# Adafruit_WINC1500_Breakout.net
KiCad netlist of a schematic drawn in EAGLE
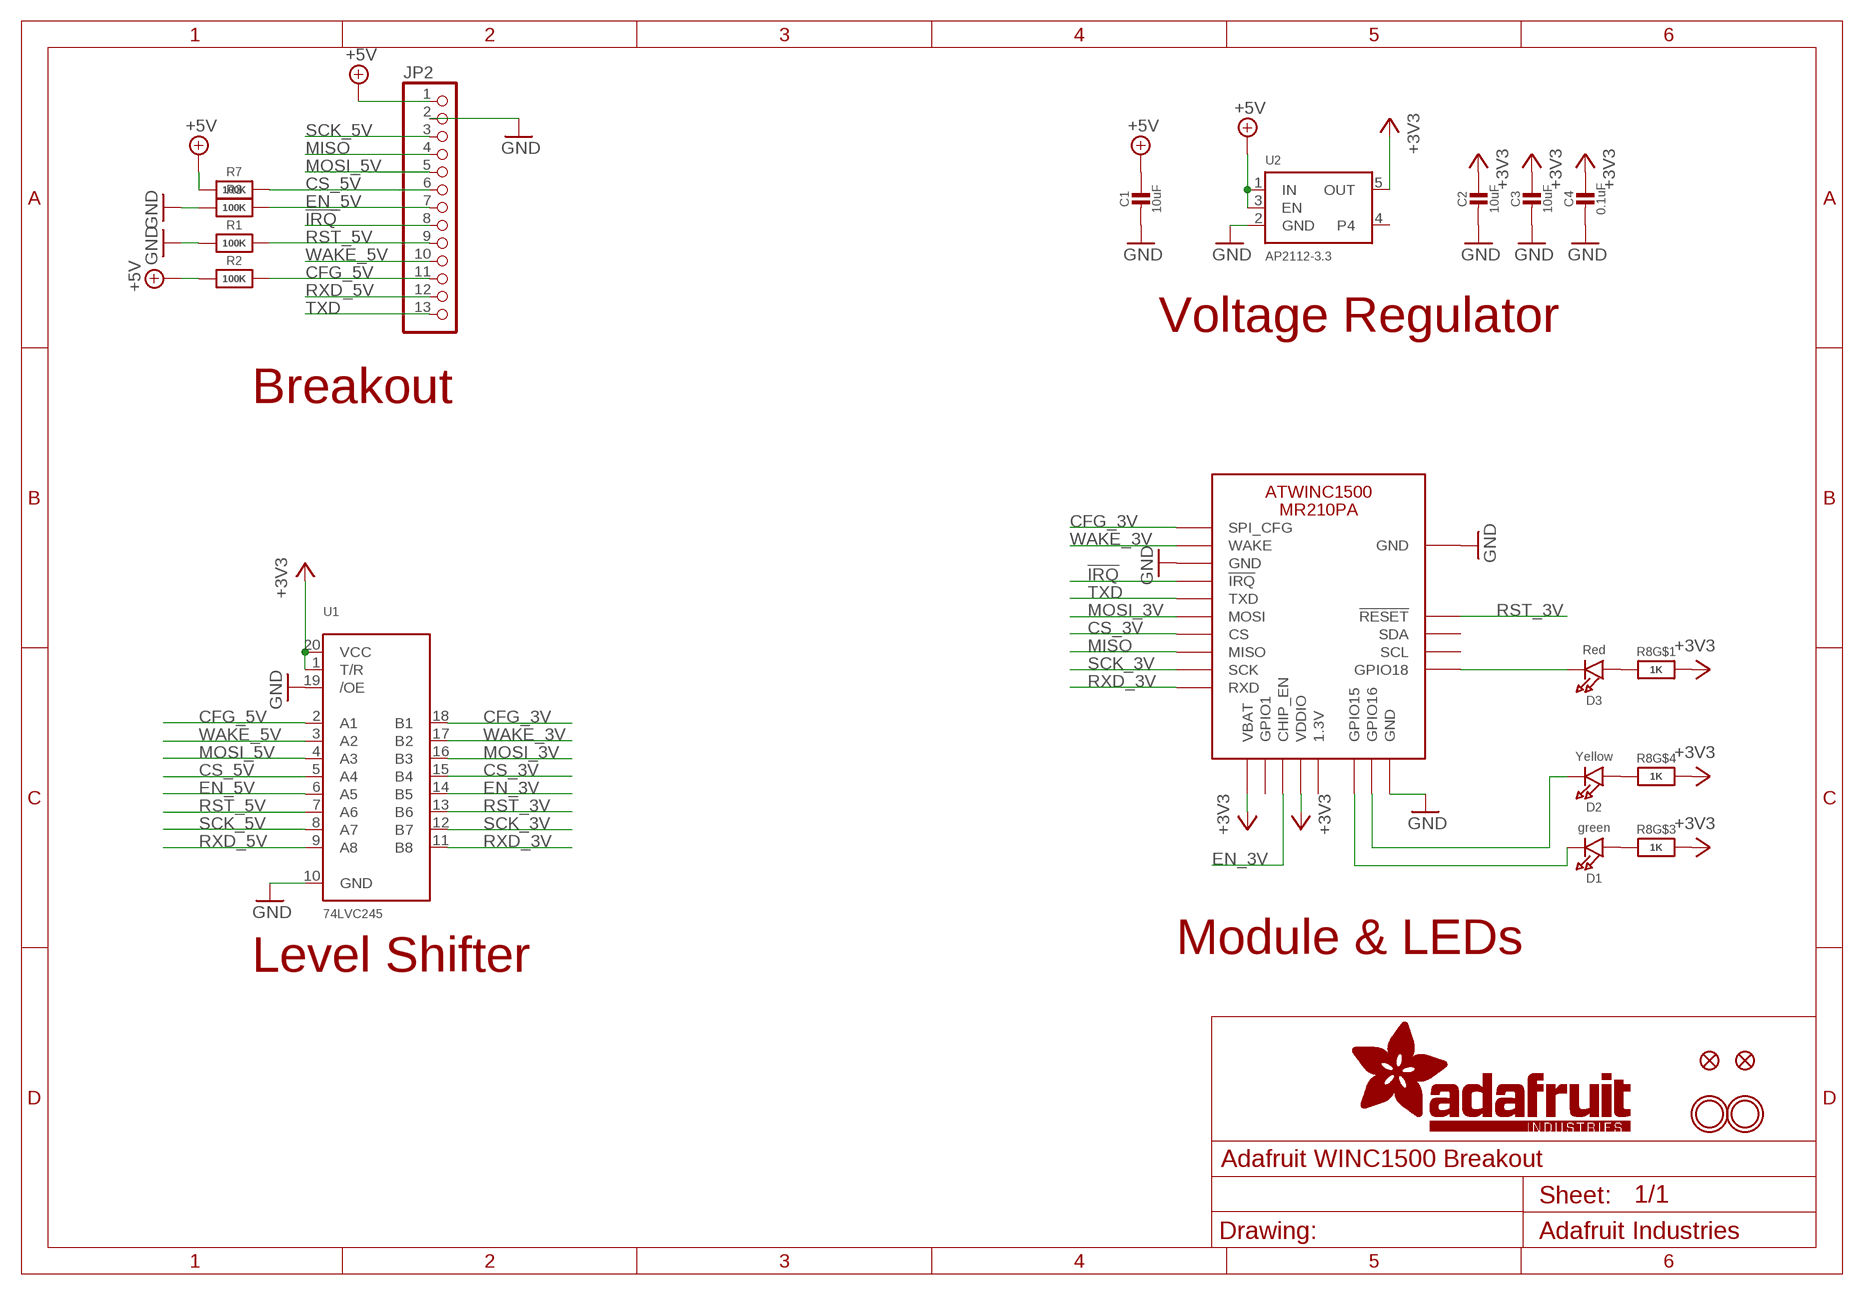
[diagram p0: schematic, sheet 1]

(export (version "E")
  (design (tool "Eeschema 10.0.6"))
  (components
    (comp (ref "C1")
      (value "10uF")
      (footprint "eagle-import:0805-NO")
      (libsource (lib "eagle-import") (part "CAP_CERAMIC0805-NOOUTLINE"))
    )
    (comp (ref "C2")
      (value "10uF")
      (footprint "eagle-import:0805_10MGAP")
      (libsource (lib "eagle-import") (part "CAP_CERAMIC0805_10MGAP"))
    )
    (comp (ref "C3")
      (value "10uF")
      (footprint "eagle-import:0805-NO")
      (libsource (lib "eagle-import") (part "CAP_CERAMIC0805-NOOUTLINE"))
    )
    (comp (ref "C4")
      (value "0.1uF")
      (footprint "eagle-import:0805-NO")
      (libsource (lib "eagle-import") (part "CAP_CERAMIC0805-NOOUTLINE"))
    )
    (comp (ref "D1")
      (value "green")
      (footprint "eagle-import:CHIPLED_0805_NOOUTLINE")
      (libsource (lib "eagle-import") (part "LED0805_NOOUTLINE"))
    )
    (comp (ref "D2")
      (value "Yellow")
      (footprint "eagle-import:CHIPLED_0805_NOOUTLINE")
      (libsource (lib "eagle-import") (part "LED0805_NOOUTLINE"))
    )
    (comp (ref "D3")
      (value "Red")
      (footprint "eagle-import:CHIPLED_0805_NOOUTLINE")
      (libsource (lib "eagle-import") (part "LED0805_NOOUTLINE"))
    )
    (comp (ref "FID1")
      (value "FIDUCIAL\"\"")
      (footprint "eagle-import:FIDUCIAL_1MM")
      (libsource (lib "eagle-import") (part "FIDUCIAL{dblquote}{dblquote}"))
    )
    (comp (ref "FID2")
      (value "FIDUCIAL\"\"")
      (footprint "eagle-import:FIDUCIAL_1MM")
      (libsource (lib "eagle-import") (part "FIDUCIAL{dblquote}{dblquote}"))
    )
    (comp (ref "JP2")
      (value "HEADER-1X13")
      (footprint "eagle-import:1X13_ROUND_70")
      (libsource (lib "eagle-import") (part "HEADER-1X13"))
    )
    (comp (ref "R1")
      (value "100K")
      (footprint "eagle-import:0805-NO")
      (libsource (lib "eagle-import") (part "RESISTOR0805_NOOUTLINE"))
    )
    (comp (ref "R2")
      (value "100K")
      (footprint "eagle-import:0805-NO")
      (libsource (lib "eagle-import") (part "RESISTOR0805_NOOUTLINE"))
    )
    (comp (ref "R3")
      (value "100K")
      (footprint "eagle-import:_0805MP")
      (libsource (lib "eagle-import") (part "RESISTOR_0805MP"))
    )
    (comp (ref "R7")
      (value "100K")
      (footprint "eagle-import:_0805MP")
      (libsource (lib "eagle-import") (part "RESISTOR_0805MP"))
    )
    (comp (ref "R8")
      (value "1K")
      (footprint "eagle-import:RESPACK_4X0603")
      (libsource (lib "eagle-import") (part "RESISTOR_4PACK"))
    )
    (comp (ref "U$1")
      (value "ATWINC1500_MR210PB")
      (footprint "eagle-import:ATWINC1500_MR210PA")
      (libsource (lib "eagle-import") (part "ATWINC1500_MR210PA"))
    )
    (comp (ref "U$2")
      (value "MOUNTINGHOLE2.5")
      (footprint "eagle-import:MOUNTINGHOLE_2.5_PLATED")
      (libsource (lib "eagle-import") (part "MOUNTINGHOLE2.5"))
    )
    (comp (ref "U$3")
      (value "MOUNTINGHOLE2.5")
      (footprint "eagle-import:MOUNTINGHOLE_2.5_PLATED")
      (libsource (lib "eagle-import") (part "MOUNTINGHOLE2.5"))
    )
    (comp (ref "U1")
      (value "74LVC245")
      (footprint "eagle-import:TSSOP20")
      (libsource (lib "eagle-import") (part "74LCX245"))
    )
    (comp (ref "U2")
      (value "AP2112-3.3")
      (footprint "eagle-import:SOT23-5")
      (libsource (lib "eagle-import") (part "VREG_SOT23-5"))
    )
  )
  (nets
    (net (code "1") (name "+3V3") (class "Default")
      (node (ref "C2") (pin "1") (pinfunction "1_1") (pintype "passive"))
      (node (ref "C3") (pin "1") (pinfunction "1_1") (pintype "passive"))
      (node (ref "C4") (pin "1") (pinfunction "1_1") (pintype "passive"))
      (node (ref "R8") (pin "5") (pinfunction "2_5") (pintype "passive"))
      (node (ref "R8") (pin "6") (pinfunction "2_6") (pintype "passive"))
      (node (ref "R8") (pin "8") (pinfunction "2_8") (pintype "passive"))
      (node (ref "U$1") (pin "J20") (pinfunction "VBAT_J20") (pintype "power_in"))
      (node (ref "U$1") (pin "J23") (pinfunction "VDDIO_J23") (pintype "power_in"))
      (node (ref "U1") (pin "1") (pinfunction "T/R_1") (pintype "bidirectional"))
      (node (ref "U1") (pin "20") (pinfunction "VCC_20") (pintype "bidirectional"))
      (node (ref "U2") (pin "5") (pinfunction "OUT_5") (pintype "power_in"))
    )
    (net (code "2") (name "+5V") (class "Default")
      (node (ref "C1") (pin "1") (pinfunction "1_1") (pintype "passive"))
      (node (ref "JP2") (pin "1") (pinfunction "1_1") (pintype "passive"))
      (node (ref "R2") (pin "1") (pinfunction "1_1") (pintype "passive"))
      (node (ref "R7") (pin "1") (pinfunction "1_1") (pintype "passive"))
      (node (ref "U2") (pin "1") (pinfunction "IN_1") (pintype "power_in"))
      (node (ref "U2") (pin "3") (pinfunction "EN_3") (pintype "input"))
    )
    (net (code "3") (name "/CFG_3V") (class "Default")
      (node (ref "U$1") (pin "J10") (pinfunction "SPI_CFG_J10") (pintype "input"))
      (node (ref "U1") (pin "18") (pinfunction "B1_18") (pintype "bidirectional"))
    )
    (net (code "4") (name "/CFG_5V") (class "Default")
      (node (ref "JP2") (pin "11") (pinfunction "11_11") (pintype "passive"))
      (node (ref "R2") (pin "2") (pinfunction "2_2") (pintype "passive"))
      (node (ref "U1") (pin "2") (pinfunction "A1_2") (pintype "bidirectional"))
    )
    (net (code "5") (name "/CS_3V") (class "Default")
      (node (ref "U$1") (pin "J16") (pinfunction "CS_J16") (pintype "input"))
      (node (ref "U1") (pin "15") (pinfunction "B4_15") (pintype "bidirectional"))
    )
    (net (code "6") (name "/CS_5V") (class "Default")
      (node (ref "JP2") (pin "6") (pinfunction "6_6") (pintype "passive"))
      (node (ref "R7") (pin "2") (pinfunction "2_2") (pintype "passive"))
      (node (ref "U1") (pin "5") (pinfunction "A4_5") (pintype "bidirectional"))
    )
    (net (code "7") (name "/EN_3V") (class "Default")
      (node (ref "U$1") (pin "J22") (pinfunction "CHIP_EN_J22") (pintype "input"))
      (node (ref "U1") (pin "14") (pinfunction "B5_14") (pintype "bidirectional"))
    )
    (net (code "8") (name "/EN_5V") (class "Default")
      (node (ref "JP2") (pin "7") (pinfunction "7_7") (pintype "passive"))
      (node (ref "R3") (pin "2") (pinfunction "2_2") (pintype "passive"))
      (node (ref "U1") (pin "6") (pinfunction "A5_6") (pintype "bidirectional"))
    )
    (net (code "9") (name "/MISO") (class "Default")
      (node (ref "JP2") (pin "4") (pinfunction "4_4") (pintype "passive"))
      (node (ref "U$1") (pin "J17") (pinfunction "MISO_J17") (pintype "output"))
    )
    (net (code "10") (name "/MOSI_3V") (class "Default")
      (node (ref "U$1") (pin "J15") (pinfunction "MOSI_J15") (pintype "input"))
      (node (ref "U1") (pin "16") (pinfunction "B3_16") (pintype "bidirectional"))
    )
    (net (code "11") (name "/MOSI_5V") (class "Default")
      (node (ref "JP2") (pin "5") (pinfunction "5_5") (pintype "passive"))
      (node (ref "U1") (pin "4") (pinfunction "A3_4") (pintype "bidirectional"))
    )
    (net (code "12") (name "/RST_3V") (class "Default")
      (node (ref "U$1") (pin "J4") (pinfunction "~{RESET}_J4") (pintype "input"))
      (node (ref "U1") (pin "13") (pinfunction "B6_13") (pintype "bidirectional"))
    )
    (net (code "13") (name "/RST_5V") (class "Default")
      (node (ref "JP2") (pin "9") (pinfunction "9_9") (pintype "passive"))
      (node (ref "R1") (pin "2") (pinfunction "2_2") (pintype "passive"))
      (node (ref "U1") (pin "7") (pinfunction "A6_7") (pintype "bidirectional"))
    )
    (net (code "14") (name "/RXD_3V") (class "Default")
      (node (ref "U$1") (pin "J19") (pinfunction "RXD_J19") (pintype "input"))
      (node (ref "U1") (pin "11") (pinfunction "B8_11") (pintype "bidirectional"))
    )
    (net (code "15") (name "/RXD_5V") (class "Default")
      (node (ref "JP2") (pin "12") (pinfunction "12_12") (pintype "passive"))
      (node (ref "U1") (pin "9") (pinfunction "A8_9") (pintype "bidirectional"))
    )
    (net (code "16") (name "/SCK_3V") (class "Default")
      (node (ref "U$1") (pin "J18") (pinfunction "SCK_J18") (pintype "input"))
      (node (ref "U1") (pin "12") (pinfunction "B7_12") (pintype "bidirectional"))
    )
    (net (code "17") (name "/SCK_5V") (class "Default")
      (node (ref "JP2") (pin "3") (pinfunction "3_3") (pintype "passive"))
      (node (ref "U1") (pin "8") (pinfunction "A7_8") (pintype "bidirectional"))
    )
    (net (code "18") (name "/TXD") (class "Default")
      (node (ref "JP2") (pin "13") (pinfunction "13_13") (pintype "passive"))
      (node (ref "U$1") (pin "J14") (pinfunction "TXD_J14") (pintype "output"))
    )
    (net (code "19") (name "/WAKE_3V") (class "Default")
      (node (ref "U$1") (pin "J11") (pinfunction "WAKE_J11") (pintype "input"))
      (node (ref "U1") (pin "17") (pinfunction "B2_17") (pintype "bidirectional"))
    )
    (net (code "20") (name "/WAKE_5V") (class "Default")
      (node (ref "JP2") (pin "10") (pinfunction "10_10") (pintype "passive"))
      (node (ref "U1") (pin "3") (pinfunction "A2_3") (pintype "bidirectional"))
    )
    (net (code "21") (name "/~{IRQ}") (class "Default")
      (node (ref "JP2") (pin "8") (pinfunction "8_8") (pintype "passive"))
      (node (ref "U$1") (pin "J13") (pinfunction "~{IRQ}_J13") (pintype "output"))
    )
    (net (code "22") (name "GND") (class "Default")
      (node (ref "C1") (pin "2") (pinfunction "2_2") (pintype "passive"))
      (node (ref "C2") (pin "2") (pinfunction "2_2") (pintype "passive"))
      (node (ref "C3") (pin "2") (pinfunction "2_2") (pintype "passive"))
      (node (ref "C4") (pin "2") (pinfunction "2_2") (pintype "passive"))
      (node (ref "JP2") (pin "2") (pinfunction "2_2") (pintype "passive"))
      (node (ref "R1") (pin "1") (pinfunction "1_1") (pintype "passive"))
      (node (ref "R3") (pin "1") (pinfunction "1_1") (pintype "passive"))
      (node (ref "U$1") (pin "J12") (pinfunction "GND_J12") (pintype "power_in"))
      (node (ref "U$1") (pin "J28") (pinfunction "GND_J28") (pintype "power_in"))
      (node (ref "U$1") (pin "J9") (pinfunction "GND_J9") (pintype "bidirectional"))
      (node (ref "U$1") (pin "MTGND") (pinfunction "GND_MTGND") (pintype "power_in"))
      (node (ref "U1") (pin "10") (pinfunction "GND_10") (pintype "bidirectional"))
      (node (ref "U1") (pin "19") (pinfunction "/OE_19") (pintype "bidirectional"))
      (node (ref "U2") (pin "2") (pinfunction "GND_2") (pintype "power_in"))
    )
    (net (code "23") (name "Net-(D3-PadA)") (class "Default")
      (node (ref "D3") (pin "A") (pinfunction "A_A") (pintype "passive"))
      (node (ref "R8") (pin "1") (pinfunction "1_1") (pintype "passive"))
    )
    (net (code "24") (name "Net-(R8C-1)") (class "Default")
      (node (ref "D1") (pin "A") (pinfunction "A_A") (pintype "passive"))
      (node (ref "R8") (pin "3") (pinfunction "1_3") (pintype "passive"))
    )
    (net (code "25") (name "Net-(R8D-1)") (class "Default")
      (node (ref "D2") (pin "A") (pinfunction "A_A") (pintype "passive"))
      (node (ref "R8") (pin "4") (pinfunction "1_4") (pintype "passive"))
    )
    (net (code "26") (name "Net-(U$1-GPIO15)") (class "Default")
      (node (ref "D1") (pin "C") (pinfunction "C_C") (pintype "passive"))
      (node (ref "U$1") (pin "J26") (pinfunction "GPIO15_J26") (pintype "bidirectional"))
    )
    (net (code "27") (name "Net-(U$1-GPIO16)") (class "Default")
      (node (ref "D2") (pin "C") (pinfunction "C_C") (pintype "passive"))
      (node (ref "U$1") (pin "J27") (pinfunction "GPIO16_J27") (pintype "bidirectional"))
    )
    (net (code "28") (name "Net-(U$1-GPIO18)") (class "Default")
      (node (ref "D3") (pin "C") (pinfunction "C_C") (pintype "passive"))
      (node (ref "U$1") (pin "J1") (pinfunction "GPIO18_J1") (pintype "bidirectional"))
    )
    (net (code "29") (name "unconnected-(U$1-1.3V-PadJ24)") (class "Default")
      (node (ref "U$1") (pin "J24") (pinfunction "1.3V_J24") (pintype "passive"))
    )
    (net (code "30") (name "unconnected-(U$1-GPIO1-PadJ21)") (class "Default")
      (node (ref "U$1") (pin "J21") (pinfunction "GPIO1_J21") (pintype "bidirectional"))
    )
    (net (code "31") (name "unconnected-(U$1-SCL-PadJ2)") (class "Default")
      (node (ref "U$1") (pin "J2") (pinfunction "SCL_J2") (pintype "bidirectional"))
    )
    (net (code "32") (name "unconnected-(U$1-SDA-PadJ3)") (class "Default")
      (node (ref "U$1") (pin "J3") (pinfunction "SDA_J3") (pintype "bidirectional"))
    )
    (net (code "33") (name "unconnected-(U2-P4-Pad4)") (class "Default")
      (node (ref "U2") (pin "4") (pinfunction "P4_4") (pintype "bidirectional"))
    )
  )
)
